# 51_STC89C52RC.net
KiCad netlist of a schematic drawn in EasyEDA Pro
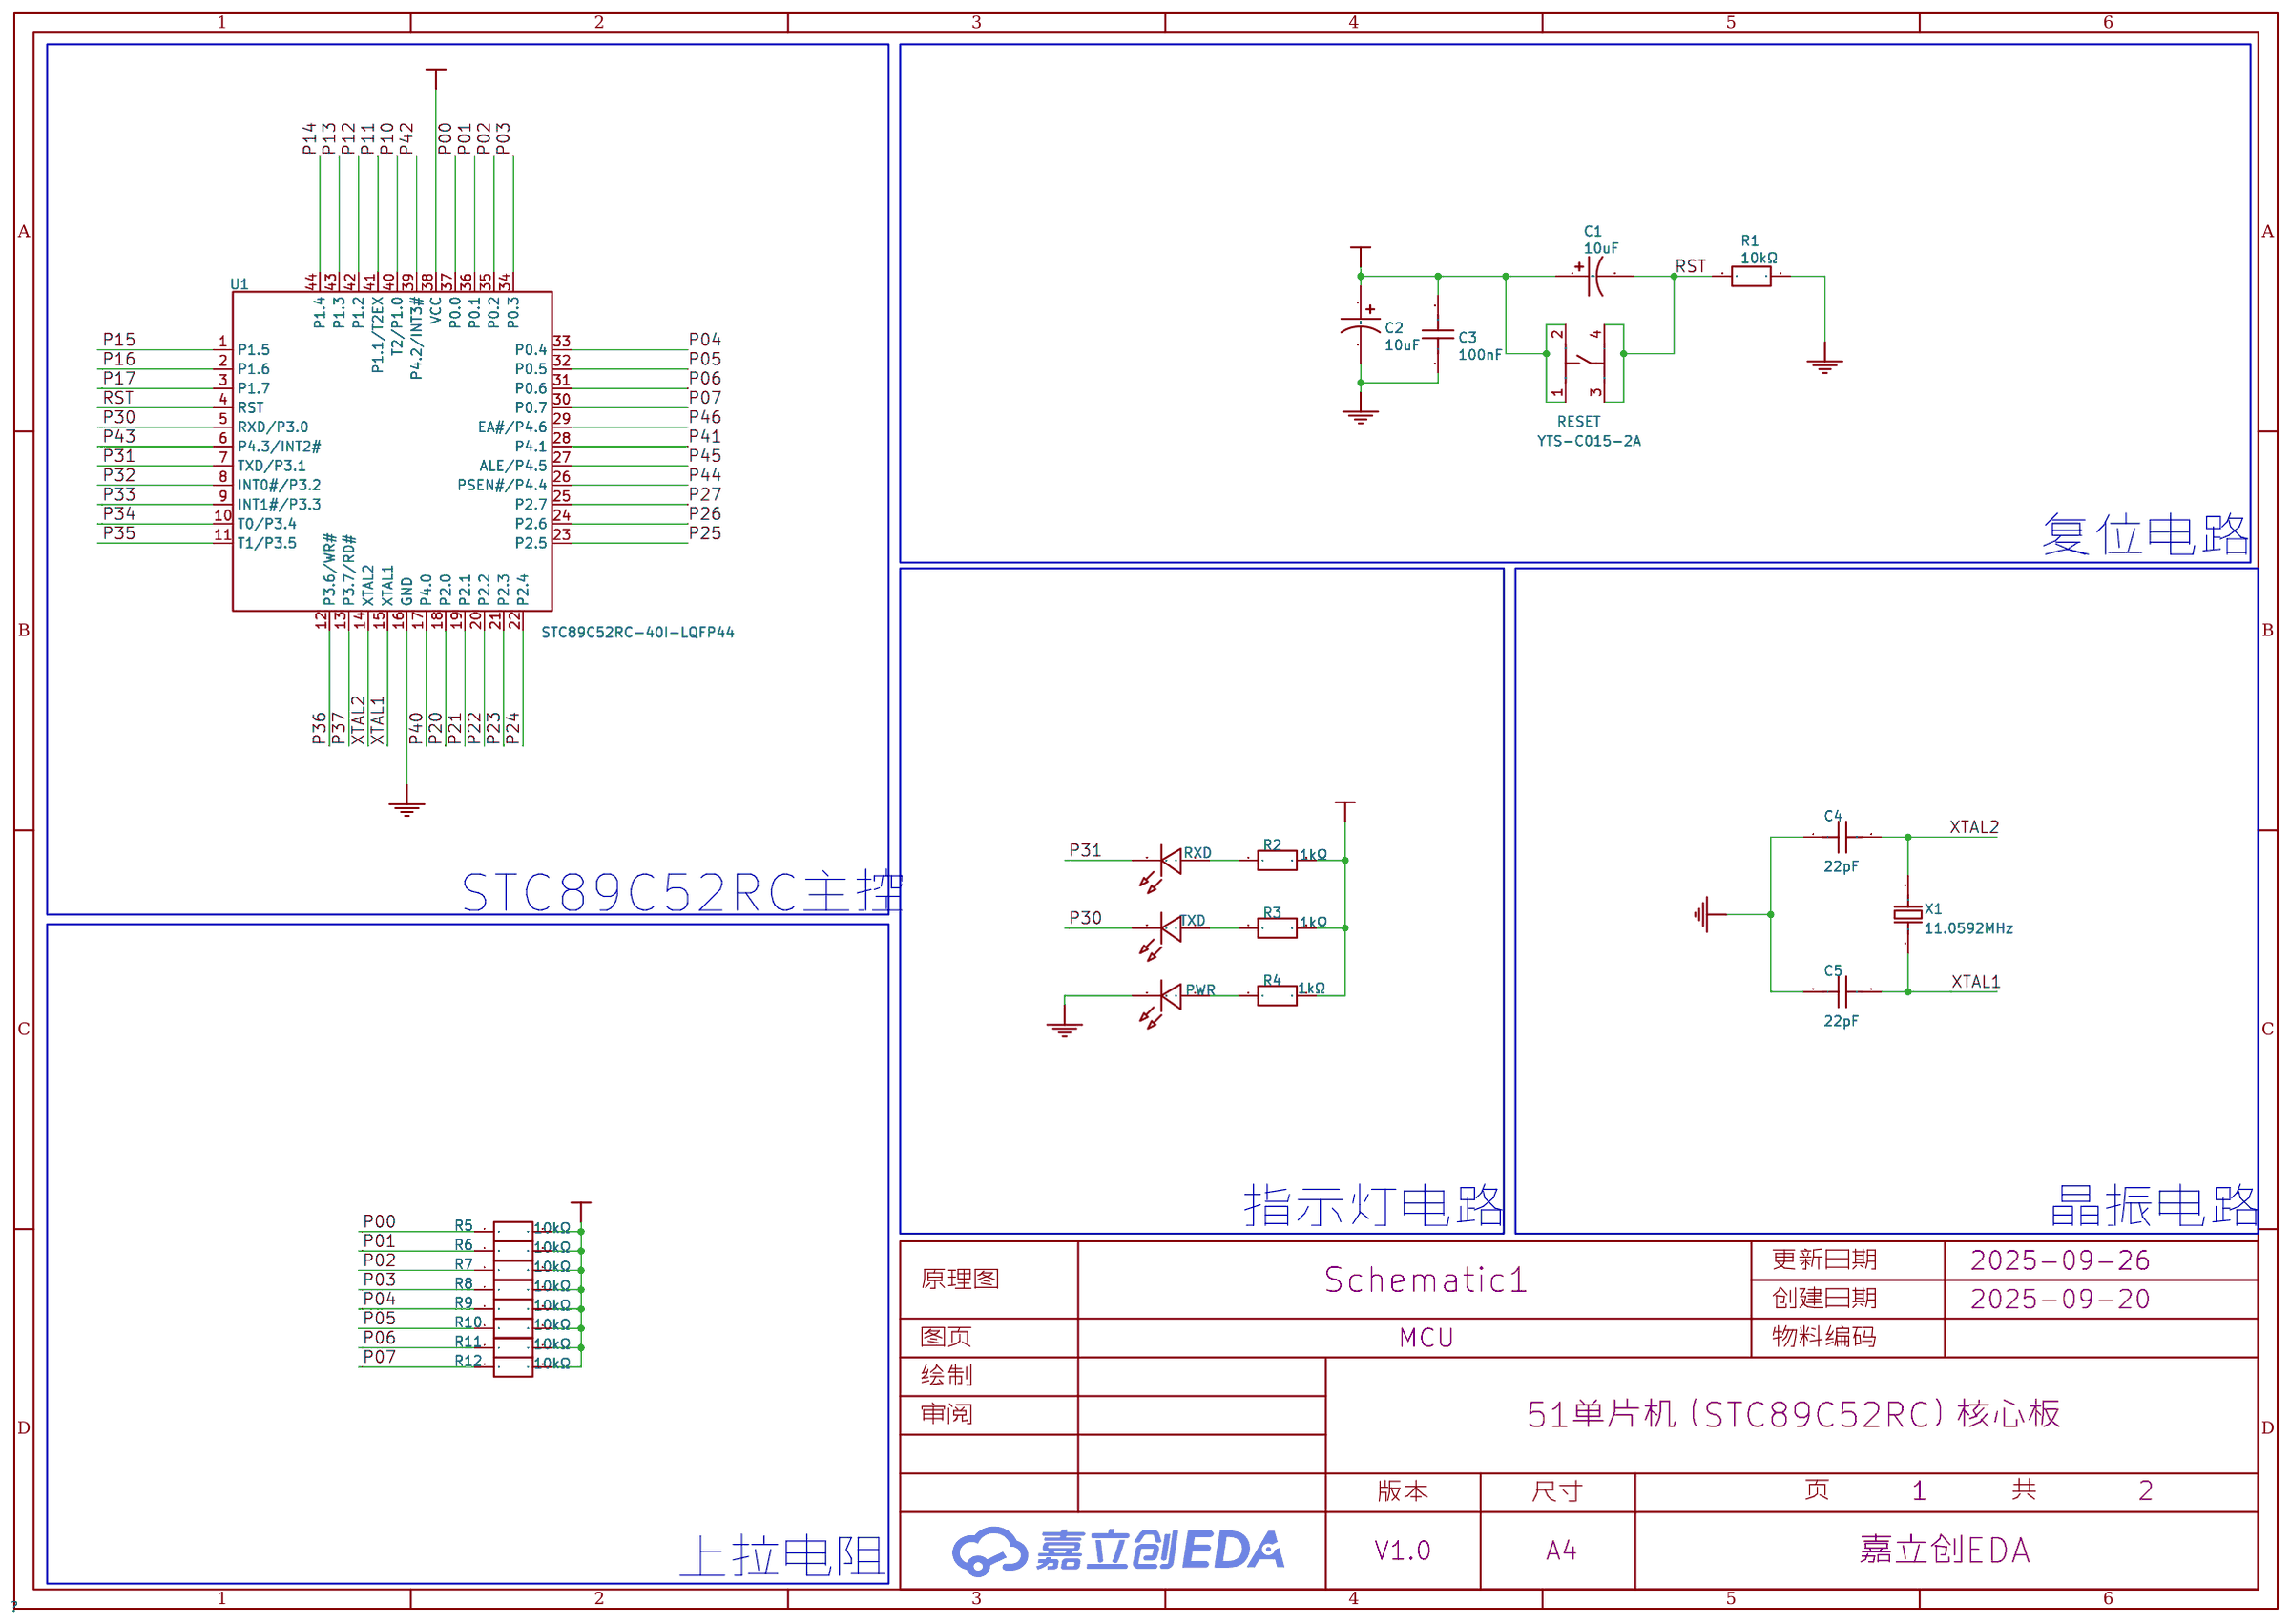
[diagram p0: MCU]
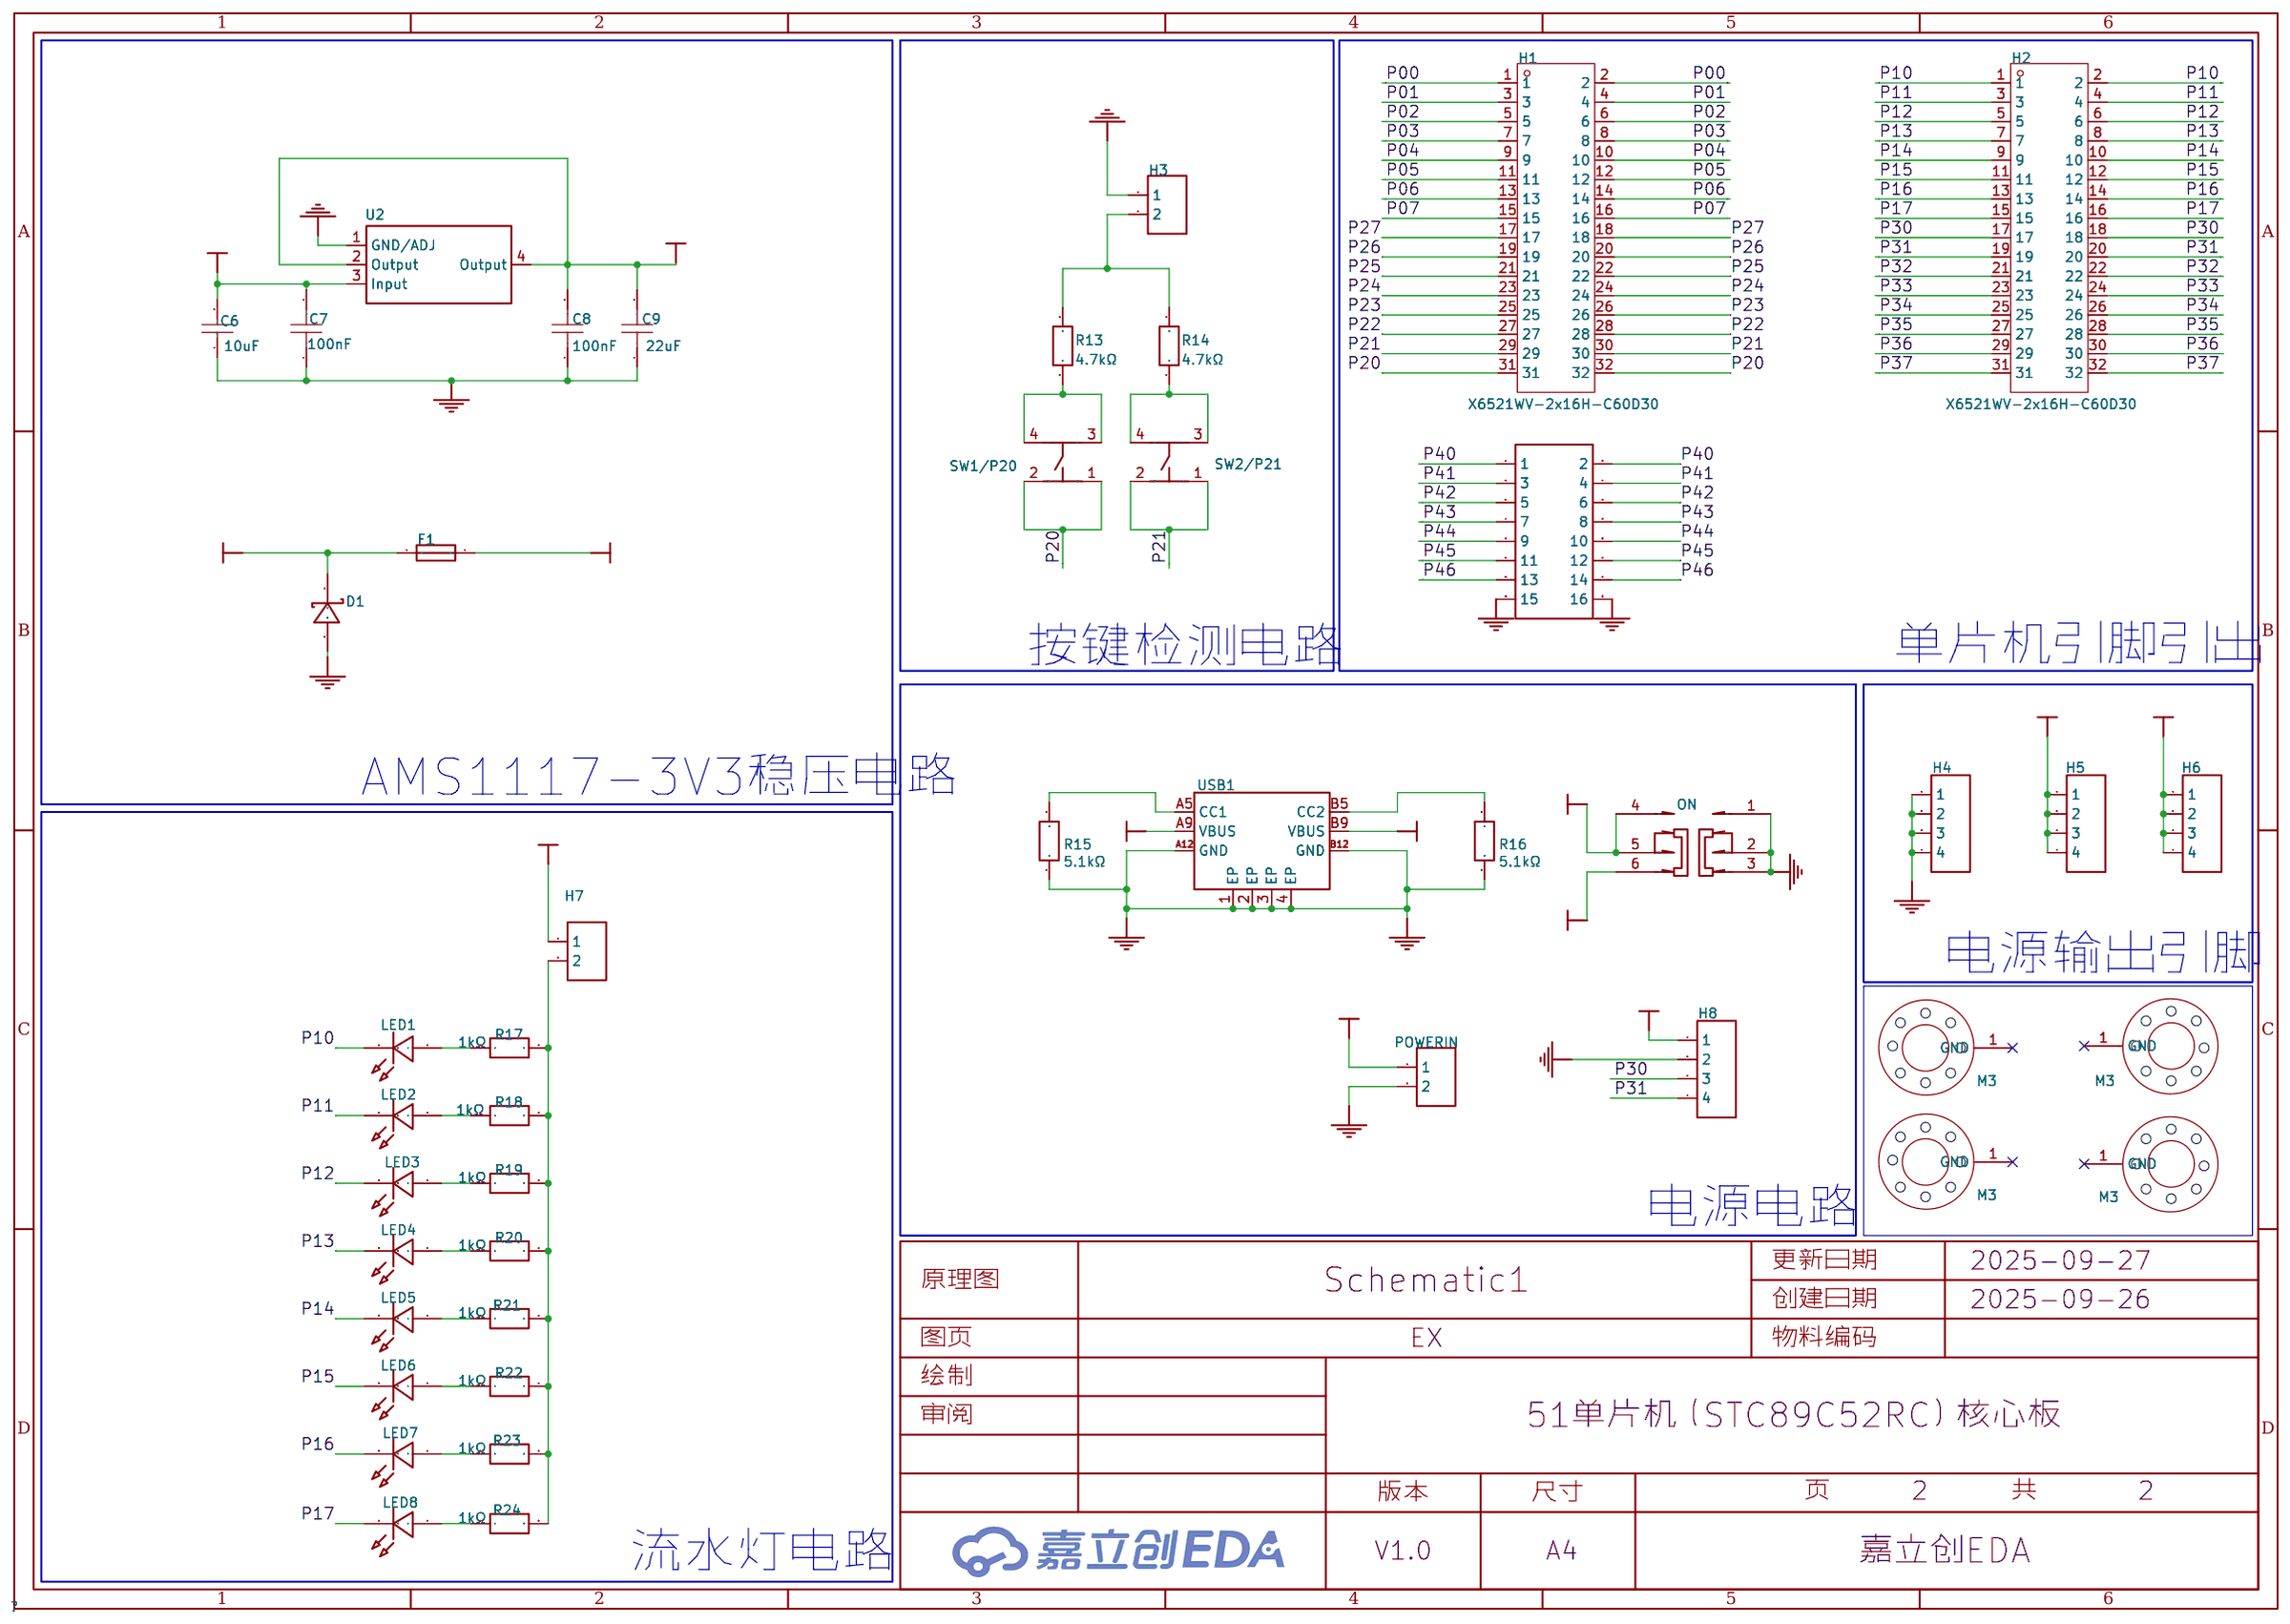
[diagram p1: EX]

(export (version "E")
  (design (tool "Eeschema 10.0.6"))
  (components
    (comp (ref "C1")
      (value "10uF")
      (footprint "easyedapro:CASE-A_3216")
      (fields (field (name "Manufacturer Part") "TAJA106K010RNJ") (field (name "Manufacturer") "Kyocera AVX"))
      (libsource (lib "easyedapro") (part "10u"))
    )
    (comp (ref "C2")
      (value "10uF")
      (footprint "easyedapro:CASE-A_3216")
      (fields (field (name "Manufacturer Part") "TAJA106K010RNJ") (field (name "Manufacturer") "Kyocera AVX"))
      (libsource (lib "") (part "10u_1"))
    )
    (comp (ref "C3")
      (value "100nF")
      (footprint "easyedapro:C0805")
      (fields
        (field (name "Manufacturer Part") "CC0805KRX7R9BB104")
        (field (name "Manufacturer") "YAGEO(国巨)")
      )
      (libsource (lib "easyedapro") (part "0.1u"))
    )
    (comp (ref "C4")
      (value "22pF")
      (footprint "easyedapro:C0805")
      (fields
        (field (name "Manufacturer Part") "CL21C220JBANNNC")
        (field (name "Manufacturer") "SAMSUNG(三星)")
      )
      (libsource (lib "easyedapro") (part "22p"))
    )
    (comp (ref "C5")
      (value "22pF")
      (footprint "easyedapro:C0805")
      (fields
        (field (name "Manufacturer Part") "CL21C220JBANNNC")
        (field (name "Manufacturer") "SAMSUNG(三星)")
      )
      (libsource (lib "easyedapro") (part "22p"))
    )
    (comp (ref "PWR")
      (value "D-B080508B1-KS2")
      (footprint "easyedapro:LED0805_BLUE")
      (fields (field (name "Manufacturer") "ARKLED(方舟)"))
      (libsource (lib "easyedapro") (part "LED-0805_B"))
    )
    (comp (ref "R1")
      (value "10kΩ")
      (footprint "easyedapro:R0805")
      (fields
        (field (name "Manufacturer Part") "0805W8F1002T5E")
        (field (name "Manufacturer") "UNI-ROYAL(厚声)")
      )
      (libsource (lib "easyedapro") (part "10k"))
    )
    (comp (ref "R2")
      (value "1kΩ")
      (footprint "easyedapro:R0805")
      (fields
        (field (name "Manufacturer Part") "0805W8F1001T5E")
        (field (name "Manufacturer") "UNI-ROYAL(厚声)")
      )
      (libsource (lib "easyedapro") (part "1k"))
    )
    (comp (ref "R3")
      (value "1kΩ")
      (footprint "easyedapro:R0805")
      (fields
        (field (name "Manufacturer Part") "0805W8F1001T5E")
        (field (name "Manufacturer") "UNI-ROYAL(厚声)")
      )
      (libsource (lib "easyedapro") (part "1k"))
    )
    (comp (ref "R4")
      (value "1kΩ")
      (footprint "easyedapro:R0805")
      (fields
        (field (name "Manufacturer Part") "0805W8F1001T5E")
        (field (name "Manufacturer") "UNI-ROYAL(厚声)")
      )
      (libsource (lib "easyedapro") (part "1k"))
    )
    (comp (ref "R5")
      (value "10kΩ")
      (footprint "easyedapro:R0805")
      (fields
        (field (name "Manufacturer Part") "0805W8F1002T5E")
        (field (name "Manufacturer") "UNI-ROYAL(厚声)")
      )
      (libsource (lib "easyedapro") (part "10k"))
    )
    (comp (ref "R6")
      (value "10kΩ")
      (footprint "easyedapro:R0805")
      (fields
        (field (name "Manufacturer Part") "0805W8F1002T5E")
        (field (name "Manufacturer") "UNI-ROYAL(厚声)")
      )
      (libsource (lib "easyedapro") (part "10k"))
    )
    (comp (ref "R7")
      (value "10kΩ")
      (footprint "easyedapro:R0805")
      (fields
        (field (name "Manufacturer Part") "0805W8F1002T5E")
        (field (name "Manufacturer") "UNI-ROYAL(厚声)")
      )
      (libsource (lib "easyedapro") (part "10k"))
    )
    (comp (ref "R8")
      (value "10kΩ")
      (footprint "easyedapro:R0805")
      (fields
        (field (name "Manufacturer Part") "0805W8F1002T5E")
        (field (name "Manufacturer") "UNI-ROYAL(厚声)")
      )
      (libsource (lib "easyedapro") (part "10k"))
    )
    (comp (ref "R9")
      (value "10kΩ")
      (footprint "easyedapro:R0805")
      (fields
        (field (name "Manufacturer Part") "0805W8F1002T5E")
        (field (name "Manufacturer") "UNI-ROYAL(厚声)")
      )
      (libsource (lib "easyedapro") (part "10k"))
    )
    (comp (ref "R10")
      (value "10kΩ")
      (footprint "easyedapro:R0805")
      (fields
        (field (name "Manufacturer Part") "0805W8F1002T5E")
        (field (name "Manufacturer") "UNI-ROYAL(厚声)")
      )
      (libsource (lib "easyedapro") (part "10k"))
    )
    (comp (ref "R11")
      (value "10kΩ")
      (footprint "easyedapro:R0805")
      (fields
        (field (name "Manufacturer Part") "0805W8F1002T5E")
        (field (name "Manufacturer") "UNI-ROYAL(厚声)")
      )
      (libsource (lib "easyedapro") (part "10k"))
    )
    (comp (ref "R12")
      (value "10kΩ")
      (footprint "easyedapro:R0805")
      (fields
        (field (name "Manufacturer Part") "0805W8F1002T5E")
        (field (name "Manufacturer") "UNI-ROYAL(厚声)")
      )
      (libsource (lib "easyedapro") (part "10k"))
    )
    (comp (ref "RESET")
      (value "YTS-C015-2A")
      (footprint "easyedapro:SW-SMD_4P-L4.5-W4.5-P3.00-LS6.8")
      (fields (field (name "Manufacturer") "YIYUAN(怡远)"))
      (libsource (lib "easyedapro") (part "YTS-C015-2A COPY"))
    )
    (comp (ref "RXD")
      (value "D-B080508B1-KS2")
      (footprint "easyedapro:LED0805_BLUE")
      (fields (field (name "Manufacturer") "ARKLED(方舟)"))
      (libsource (lib "easyedapro") (part "LED-0805_B"))
    )
    (comp (ref "TXD")
      (value "D-B080508B1-KS2")
      (footprint "easyedapro:LED0805_BLUE")
      (fields (field (name "Manufacturer") "ARKLED(方舟)"))
      (libsource (lib "easyedapro") (part "LED-0805_B"))
    )
    (comp (ref "U1")
      (value "STC89C52RC-40I-LQFP44")
      (footprint "easyedapro:LQFP-44_L10.0-W10.0-P0.80-LS12.0-BL")
      (fields (field (name "Manufacturer") "STC"))
      (libsource (lib "easyedapro") (part "STC89C52RC-40I_C8707"))
    )
    (comp (ref "X1")
      (value "11.0592MHz")
      (footprint "easyedapro:HC-49US_L11.5-W4.5-P4.88")
      (fields
        (field (name "Manufacturer Part") "TAXD11.0592M2GLFBET2T")
        (field (name "Manufacturer") "YJX(雅晶鑫)")
      )
      (libsource (lib "easyedapro") (part "11.0592MHz"))
    )
    (comp (ref "C6")
      (value "10uF")
      (footprint "easyedapro:C0805")
      (description "容值:10uF;精度:±10%;额定电压:16V;温度系数:X5R;")
      (fields
        (field (name "Manufacturer Part") "CL21A106KOQNNNE")
        (field (name "Manufacturer") "SAMSUNG(三星)")
      )
      (libsource (lib "easyedapro") (part "CL21A106KOQNNNE"))
    )
    (comp (ref "C7")
      (value "100nF")
      (footprint "easyedapro:C0805")
      (description "容值:100nF;精度:±10%;额定电压:50V;温度系数:X7R;")
      (fields
        (field (name "Manufacturer Part") "FCC0805B104K500DT")
        (field (name "Manufacturer") "FOJAN(富捷)")
      )
      (libsource (lib "easyedapro") (part "FCC0805B104K500DT"))
    )
    (comp (ref "C8")
      (value "100nF")
      (footprint "easyedapro:C0805")
      (description "容值:100nF;精度:±10%;额定电压:50V;温度系数:X7R;")
      (fields
        (field (name "Manufacturer Part") "FCC0805B104K500DT")
        (field (name "Manufacturer") "FOJAN(富捷)")
      )
      (libsource (lib "easyedapro") (part "FCC0805B104K500DT"))
    )
    (comp (ref "C9")
      (value "22uF")
      (footprint "easyedapro:C0805")
      (description "容值:22uF;精度:±20%;额定电压:25V;温度系数:X5R;")
      (fields
        (field (name "Manufacturer Part") "FCC0805X226M250FT")
        (field (name "Manufacturer") "FOJAN(富捷)")
      )
      (libsource (lib "easyedapro") (part "FCC0805X226M250FT"))
    )
    (comp (ref "D1")
      (value "1N5819W")
      (footprint "easyedapro:SOD-123F_L2.8-W1.8-LS3.7-RD")
      (fields (field (name "Manufacturer") "Shandong Jingdao Microelectronics"))
      (libsource (lib "easyedapro") (part "1N5819W"))
    )
    (comp (ref "F1")
      (value "FSMD050-1206-R")
      (footprint "easyedapro:F1206")
      (fields (field (name "Manufacturer") "Fuzetec Tech"))
      (libsource (lib "easyedapro") (part "FSMD050-1206-R"))
    )
    (comp (ref "H1")
      (value "X6521WV-2x16H-C60D30")
      (footprint "easyedapro:HDR-TH_32P-2.54-V-M-R2-C16-S2.54")
      (fields (field (name "Manufacturer") "XKB Connection(中国星坤)"))
      (libsource (lib "easyedapro") (part "X6521WV-2×16H-C30D60"))
    )
    (comp (ref "H2")
      (value "X6521WV-2x16H-C60D30")
      (footprint "easyedapro:HDR-TH_32P-2.54-V-M-R2-C16-S2.54")
      (fields (field (name "Manufacturer") "XKB Connection(中国星坤)"))
      (libsource (lib "easyedapro") (part "X6521WV-2×16H-C30D60"))
    )
    (comp (ref "H3")
      (value "2.54-1*2P母")
      (footprint "easyedapro:HDR-M-2.54_1X2")
      (libsource (lib "") (part "HDR-F-2.54_1x2_1"))
    )
    (comp (ref "H4")
      (value "A2541HWV-4P")
      (footprint "easyedapro:HDR-F-2.54_1X4")
      (libsource (lib "easyedapro") (part "HDR-F-2.54_1x4"))
    )
    (comp (ref "H5")
      (value "A2541HWV-4P")
      (footprint "easyedapro:HDR-F-2.54_1X4")
      (libsource (lib "easyedapro") (part "HDR-F-2.54_1x4"))
    )
    (comp (ref "H6")
      (value "A2541HWV-4P")
      (footprint "easyedapro:HDR-F-2.54_1X4")
      (libsource (lib "easyedapro") (part "HDR-F-2.54_1x4"))
    )
    (comp (ref "H7")
      (value "2.54-1*2P母")
      (footprint "easyedapro:HDR-M-2.54_1X2")
      (libsource (lib "easyedapro") (part "HDR-F-2.54_1x2"))
    )
    (comp (ref "H8")
      (value "A2541HWV-4P")
      (footprint "easyedapro:HDR-F-2.54_1X4")
      (libsource (lib "easyedapro") (part "HDR-F-2.54_1x4"))
    )
    (comp (ref "hole1")
      (value "M3")
      (footprint "easyedapro:m3梅花孔")
      (description "梅花螺丝孔")
      (libsource (lib "easyedapro") (part "m3_梅花螺丝孔"))
    )
    (comp (ref "hole2")
      (value "M3")
      (footprint "easyedapro:m3梅花孔")
      (description "梅花螺丝孔")
      (libsource (lib "easyedapro") (part "m3_梅花螺丝孔"))
    )
    (comp (ref "hole3")
      (value "M3")
      (footprint "easyedapro:m3梅花孔")
      (description "梅花螺丝孔")
      (libsource (lib "easyedapro") (part "m3_梅花螺丝孔"))
    )
    (comp (ref "hole4")
      (value "M3")
      (footprint "easyedapro:m3梅花孔")
      (description "梅花螺丝孔")
      (libsource (lib "easyedapro") (part "m3_梅花螺丝孔"))
    )
    (comp (ref "J1")
      (value "2.54-2*8P针")
      (footprint "easyedapro:HDR-M-2.54_2X8")
      (fields (field (name "Manufacturer") "BOOMELE(博穆精密)"))
      (libsource (lib "easyedapro") (part "HDR-M-2.54_2x8"))
    )
    (comp (ref "LED1")
      (value "D-B080508B1-KS2")
      (footprint "easyedapro:LED0805_BLUE")
      (fields (field (name "Manufacturer") "方舟 ARKLED"))
      (libsource (lib "easyedapro") (part "LED-0805_B"))
    )
    (comp (ref "LED2")
      (value "D-B080508B1-KS2")
      (footprint "easyedapro:LED0805_BLUE")
      (fields (field (name "Manufacturer") "方舟 ARKLED"))
      (libsource (lib "easyedapro") (part "LED-0805_B"))
    )
    (comp (ref "LED3")
      (value "D-B080508B1-KS2")
      (footprint "easyedapro:LED0805_BLUE")
      (fields (field (name "Manufacturer") "方舟 ARKLED"))
      (libsource (lib "easyedapro") (part "LED-0805_B"))
    )
    (comp (ref "LED4")
      (value "D-B080508B1-KS2")
      (footprint "easyedapro:LED0805_BLUE")
      (fields (field (name "Manufacturer") "方舟 ARKLED"))
      (libsource (lib "easyedapro") (part "LED-0805_B"))
    )
    (comp (ref "LED5")
      (value "D-B080508B1-KS2")
      (footprint "easyedapro:LED0805_BLUE")
      (fields (field (name "Manufacturer") "方舟 ARKLED"))
      (libsource (lib "easyedapro") (part "LED-0805_B"))
    )
    (comp (ref "LED6")
      (value "D-B080508B1-KS2")
      (footprint "easyedapro:LED0805_BLUE")
      (fields (field (name "Manufacturer") "方舟 ARKLED"))
      (libsource (lib "easyedapro") (part "LED-0805_B"))
    )
    (comp (ref "LED7")
      (value "D-B080508B1-KS2")
      (footprint "easyedapro:LED0805_BLUE")
      (fields (field (name "Manufacturer") "方舟 ARKLED"))
      (libsource (lib "easyedapro") (part "LED-0805_B"))
    )
    (comp (ref "LED8")
      (value "D-B080508B1-KS2")
      (footprint "easyedapro:LED0805_BLUE")
      (fields (field (name "Manufacturer") "方舟 ARKLED"))
      (libsource (lib "easyedapro") (part "LED-0805_B"))
    )
    (comp (ref "ON")
      (value "SS-3235S-L1")
      (footprint "easyedapro:SW-SMD_SS-3235S-LX")
      (description "电路结构:双刀双掷;安装方式:卧贴;开关颜色:黑色;额定电流:50mA;额定电压:12V;工作寿命:1万次;")
      (fields (field (name "Manufacturer") "XKB Connection(中国星坤)"))
      (libsource (lib "easyedapro") (part "SS-3235S-L1"))
    )
    (comp (ref "POWERIN")
      (value "2.54-1*2P母")
      (footprint "easyedapro:HDR-M-2.54_1X2")
      (libsource (lib "easyedapro") (part "HDR-F-2.54_1x2"))
    )
    (comp (ref "R13")
      (value "4.7kΩ")
      (footprint "easyedapro:R0805")
      (fields (field (name "Manufacturer") "UNI-ROYAL(厚声)"))
      (libsource (lib "easyedapro") (part "4.7K"))
    )
    (comp (ref "R14")
      (value "4.7kΩ")
      (footprint "easyedapro:R0805")
      (fields (field (name "Manufacturer") "UNI-ROYAL(厚声)"))
      (libsource (lib "easyedapro") (part "4.7K"))
    )
    (comp (ref "R15")
      (value "5.1kΩ")
      (footprint "easyedapro:R0805")
      (fields (field (name "Manufacturer") "UNI-ROYAL(厚声)"))
      (libsource (lib "easyedapro") (part "5.1k"))
    )
    (comp (ref "R16")
      (value "5.1kΩ")
      (footprint "easyedapro:R0805")
      (fields (field (name "Manufacturer") "UNI-ROYAL(厚声)"))
      (libsource (lib "easyedapro") (part "5.1k"))
    )
    (comp (ref "R17")
      (value "1kΩ")
      (footprint "easyedapro:R0805")
      (fields (field (name "Manufacturer") "UNI-ROYAL(厚声)"))
      (libsource (lib "easyedapro") (part "1k"))
    )
    (comp (ref "R18")
      (value "1kΩ")
      (footprint "easyedapro:R0805")
      (fields (field (name "Manufacturer") "UNI-ROYAL(厚声)"))
      (libsource (lib "easyedapro") (part "1k"))
    )
    (comp (ref "R19")
      (value "1kΩ")
      (footprint "easyedapro:R0805")
      (fields (field (name "Manufacturer") "UNI-ROYAL(厚声)"))
      (libsource (lib "easyedapro") (part "1k"))
    )
    (comp (ref "R20")
      (value "1kΩ")
      (footprint "easyedapro:R0805")
      (fields (field (name "Manufacturer") "UNI-ROYAL(厚声)"))
      (libsource (lib "easyedapro") (part "1k"))
    )
    (comp (ref "R21")
      (value "1kΩ")
      (footprint "easyedapro:R0805")
      (fields (field (name "Manufacturer") "UNI-ROYAL(厚声)"))
      (libsource (lib "easyedapro") (part "1k"))
    )
    (comp (ref "R22")
      (value "1kΩ")
      (footprint "easyedapro:R0805")
      (fields (field (name "Manufacturer") "UNI-ROYAL(厚声)"))
      (libsource (lib "easyedapro") (part "1k"))
    )
    (comp (ref "R23")
      (value "1kΩ")
      (footprint "easyedapro:R0805")
      (fields (field (name "Manufacturer") "UNI-ROYAL(厚声)"))
      (libsource (lib "easyedapro") (part "1k"))
    )
    (comp (ref "R24")
      (value "1kΩ")
      (footprint "easyedapro:R0805")
      (fields (field (name "Manufacturer") "UNI-ROYAL(厚声)"))
      (libsource (lib "easyedapro") (part "1k"))
    )
    (comp (ref "SW1/P20")
      (value "YTS-C015-2A")
      (footprint "easyedapro:SW-SMD_4P-L4.5-W4.5-P3.00-LS6.8")
      (fields (field (name "Manufacturer") "YIYUAN(怡远)"))
      (libsource (lib "easyedapro") (part "YTS-C015-2A COPY"))
    )
    (comp (ref "SW2/P21")
      (value "YTS-C015-2A")
      (footprint "easyedapro:SW-SMD_4P-L4.5-W4.5-P3.00-LS6.8")
      (fields (field (name "Manufacturer") "YIYUAN(怡远)"))
      (libsource (lib "easyedapro") (part "YTS-C015-2A COPY"))
    )
    (comp (ref "U2")
      (value "AMS1117-3.3")
      (footprint "easyedapro:SOT-223-4_L6.5-W3.5-P2.30-LS7.0-BR")
      (fields (field (name "Manufacturer") "KEXIN"))
      (libsource (lib "easyedapro") (part "AMS1117"))
    )
    (comp (ref "USB1")
      (value "KH-TYPE-C-6P")
      (footprint "easyedapro:TYPE-C-SMD_TYPE-C-31-M-16")
      (fields (field (name "Manufacturer") "Shenzhen Kinghelm Elec"))
      (libsource (lib "easyedapro") (part "KH-TYPE-C-6P"))
    )
  )
  (nets
    (net (code "1") (name "+5V") (class "Default")
      (node (ref "C1") (pin "1") (pinfunction "1_1") (pintype "unspecified"))
      (node (ref "C2") (pin "1") (pinfunction "1_1") (pintype "unspecified"))
      (node (ref "C3") (pin "2") (pinfunction "2_2") (pintype "unspecified"))
      (node (ref "C6") (pin "2") (pinfunction "2_2") (pintype "input"))
      (node (ref "C7") (pin "2") (pinfunction "2_2") (pintype "unspecified"))
      (node (ref "D1") (pin "1") (pinfunction "1_1") (pintype "unspecified"))
      (node (ref "F1") (pin "2") (pinfunction "2_2") (pintype "unspecified"))
      (node (ref "H5") (pin "1") (pinfunction "1_1") (pintype "unspecified"))
      (node (ref "H5") (pin "2") (pinfunction "2_2") (pintype "unspecified"))
      (node (ref "H5") (pin "3") (pinfunction "3_3") (pintype "unspecified"))
      (node (ref "H5") (pin "4") (pinfunction "4_4") (pintype "unspecified"))
      (node (ref "H7") (pin "1") (pinfunction "1_1") (pintype "input"))
      (node (ref "H8") (pin "1") (pinfunction "1_1") (pintype "unspecified"))
      (node (ref "R10") (pin "2") (pinfunction "2_2") (pintype "unspecified"))
      (node (ref "R11") (pin "2") (pinfunction "2_2") (pintype "unspecified"))
      (node (ref "R12") (pin "2") (pinfunction "2_2") (pintype "unspecified"))
      (node (ref "R2") (pin "2") (pinfunction "2_2") (pintype "unspecified"))
      (node (ref "R3") (pin "2") (pinfunction "2_2") (pintype "unspecified"))
      (node (ref "R4") (pin "2") (pinfunction "2_2") (pintype "unspecified"))
      (node (ref "R5") (pin "2") (pinfunction "2_2") (pintype "unspecified"))
      (node (ref "R6") (pin "2") (pinfunction "2_2") (pintype "unspecified"))
      (node (ref "R7") (pin "2") (pinfunction "2_2") (pintype "unspecified"))
      (node (ref "R8") (pin "2") (pinfunction "2_2") (pintype "unspecified"))
      (node (ref "R9") (pin "2") (pinfunction "2_2") (pintype "unspecified"))
      (node (ref "RESET") (pin "1") (pinfunction "1_1") (pintype "unspecified"))
      (node (ref "RESET") (pin "2") (pinfunction "2_2") (pintype "unspecified"))
      (node (ref "U1") (pin "38") (pinfunction "VCC_38") (pintype "unspecified"))
      (node (ref "U2") (pin "3") (pinfunction "Input_3") (pintype "unspecified"))
    )
    (net (code "2") (name "3V3") (class "Default")
      (node (ref "C8") (pin "2") (pinfunction "2_2") (pintype "unspecified"))
      (node (ref "C9") (pin "2") (pinfunction "2_2") (pintype "unspecified"))
      (node (ref "H6") (pin "1") (pinfunction "1_1") (pintype "unspecified"))
      (node (ref "H6") (pin "2") (pinfunction "2_2") (pintype "unspecified"))
      (node (ref "H6") (pin "3") (pinfunction "3_3") (pintype "unspecified"))
      (node (ref "H6") (pin "4") (pinfunction "4_4") (pintype "unspecified"))
      (node (ref "U2") (pin "2") (pinfunction "Output_2") (pintype "unspecified"))
      (node (ref "U2") (pin "4") (pinfunction "Output_4") (pintype "unspecified"))
    )
    (net (code "3") (name "GND") (class "Default")
      (node (ref "C2") (pin "2") (pinfunction "2_2") (pintype "unspecified"))
      (node (ref "C3") (pin "1") (pinfunction "1_1") (pintype "unspecified"))
      (node (ref "C4") (pin "1") (pinfunction "1_1") (pintype "unspecified"))
      (node (ref "C5") (pin "2") (pinfunction "2_2") (pintype "unspecified"))
      (node (ref "C6") (pin "1") (pinfunction "1_1") (pintype "input"))
      (node (ref "C7") (pin "1") (pinfunction "1_1") (pintype "unspecified"))
      (node (ref "C8") (pin "1") (pinfunction "1_1") (pintype "unspecified"))
      (node (ref "C9") (pin "1") (pinfunction "1_1") (pintype "unspecified"))
      (node (ref "D1") (pin "2") (pinfunction "2_2") (pintype "unspecified"))
      (node (ref "H3") (pin "1") (pinfunction "1_1") (pintype "input"))
      (node (ref "H4") (pin "1") (pinfunction "1_1") (pintype "unspecified"))
      (node (ref "H4") (pin "2") (pinfunction "2_2") (pintype "unspecified"))
      (node (ref "H4") (pin "3") (pinfunction "3_3") (pintype "unspecified"))
      (node (ref "H4") (pin "4") (pinfunction "4_4") (pintype "unspecified"))
      (node (ref "H8") (pin "2") (pinfunction "2_2") (pintype "unspecified"))
      (node (ref "J1") (pin "15") (pinfunction "15_15") (pintype "input"))
      (node (ref "J1") (pin "16") (pinfunction "16_16") (pintype "input"))
      (node (ref "ON") (pin "1") (pinfunction "1_1") (pintype "unspecified"))
      (node (ref "ON") (pin "2") (pinfunction "2_2") (pintype "unspecified"))
      (node (ref "ON") (pin "3") (pinfunction "3_3") (pintype "unspecified"))
      (node (ref "POWERIN") (pin "2") (pinfunction "2_2") (pintype "input"))
      (node (ref "PWR") (pin "2") (pinfunction "2_2") (pintype "unspecified"))
      (node (ref "R1") (pin "2") (pinfunction "2_2") (pintype "unspecified"))
      (node (ref "R15") (pin "1") (pinfunction "1_1") (pintype "unspecified"))
      (node (ref "R16") (pin "1") (pinfunction "1_1") (pintype "unspecified"))
      (node (ref "U1") (pin "16") (pinfunction "GND_16") (pintype "unspecified"))
      (node (ref "U2") (pin "1") (pinfunction "GND/ADJ_1") (pintype "unspecified"))
      (node (ref "USB1") (pin "1") (pinfunction "EP_1") (pintype "unspecified"))
      (node (ref "USB1") (pin "2") (pinfunction "EP_2") (pintype "unspecified"))
      (node (ref "USB1") (pin "3") (pinfunction "EP_3") (pintype "unspecified"))
      (node (ref "USB1") (pin "4") (pinfunction "EP_4") (pintype "unspecified"))
      (node (ref "USB1") (pin "A12") (pinfunction "GND_A12") (pintype "unspecified"))
      (node (ref "USB1") (pin "B12") (pinfunction "GND_B12") (pintype "unspecified"))
    )
    (net (code "4") (name "Net-(H3-Pad2)") (class "Default")
      (node (ref "H3") (pin "2") (pinfunction "2_2") (pintype "input"))
      (node (ref "R13") (pin "2") (pinfunction "2_2") (pintype "unspecified"))
      (node (ref "R14") (pin "2") (pinfunction "2_2") (pintype "unspecified"))
    )
    (net (code "5") (name "Net-(H7-Pad2)") (class "Default")
      (node (ref "H7") (pin "2") (pinfunction "2_2") (pintype "input"))
      (node (ref "R17") (pin "2") (pinfunction "2_2") (pintype "unspecified"))
      (node (ref "R18") (pin "2") (pinfunction "2_2") (pintype "unspecified"))
      (node (ref "R19") (pin "2") (pinfunction "2_2") (pintype "unspecified"))
      (node (ref "R20") (pin "2") (pinfunction "2_2") (pintype "unspecified"))
      (node (ref "R21") (pin "2") (pinfunction "2_2") (pintype "unspecified"))
      (node (ref "R22") (pin "2") (pinfunction "2_2") (pintype "unspecified"))
      (node (ref "R23") (pin "2") (pinfunction "2_2") (pintype "unspecified"))
      (node (ref "R24") (pin "2") (pinfunction "2_2") (pintype "unspecified"))
    )
    (net (code "6") (name "Net-(LED1-Pad1)") (class "Default")
      (node (ref "LED1") (pin "1") (pinfunction "1_1") (pintype "unspecified"))
      (node (ref "R17") (pin "1") (pinfunction "1_1") (pintype "unspecified"))
    )
    (net (code "7") (name "Net-(LED2-Pad1)") (class "Default")
      (node (ref "LED2") (pin "1") (pinfunction "1_1") (pintype "unspecified"))
      (node (ref "R18") (pin "1") (pinfunction "1_1") (pintype "unspecified"))
    )
    (net (code "8") (name "Net-(LED3-Pad1)") (class "Default")
      (node (ref "LED3") (pin "1") (pinfunction "1_1") (pintype "unspecified"))
      (node (ref "R19") (pin "1") (pinfunction "1_1") (pintype "unspecified"))
    )
    (net (code "9") (name "Net-(LED4-Pad1)") (class "Default")
      (node (ref "LED4") (pin "1") (pinfunction "1_1") (pintype "unspecified"))
      (node (ref "R20") (pin "1") (pinfunction "1_1") (pintype "unspecified"))
    )
    (net (code "10") (name "Net-(LED5-Pad1)") (class "Default")
      (node (ref "LED5") (pin "1") (pinfunction "1_1") (pintype "unspecified"))
      (node (ref "R21") (pin "1") (pinfunction "1_1") (pintype "unspecified"))
    )
    (net (code "11") (name "Net-(LED6-Pad1)") (class "Default")
      (node (ref "LED6") (pin "1") (pinfunction "1_1") (pintype "unspecified"))
      (node (ref "R22") (pin "1") (pinfunction "1_1") (pintype "unspecified"))
    )
    (net (code "12") (name "Net-(LED7-Pad1)") (class "Default")
      (node (ref "LED7") (pin "1") (pinfunction "1_1") (pintype "unspecified"))
      (node (ref "R23") (pin "1") (pinfunction "1_1") (pintype "unspecified"))
    )
    (net (code "13") (name "Net-(LED8-Pad1)") (class "Default")
      (node (ref "LED8") (pin "1") (pinfunction "1_1") (pintype "unspecified"))
      (node (ref "R24") (pin "1") (pinfunction "1_1") (pintype "unspecified"))
    )
    (net (code "14") (name "Net-(PWR-Pad1)") (class "Default")
      (node (ref "PWR") (pin "1") (pinfunction "1_1") (pintype "unspecified"))
      (node (ref "R4") (pin "1") (pinfunction "1_1") (pintype "unspecified"))
    )
    (net (code "15") (name "Net-(R2-Pad1)") (class "Default")
      (node (ref "R2") (pin "1") (pinfunction "1_1") (pintype "unspecified"))
      (node (ref "RXD") (pin "1") (pinfunction "1_1") (pintype "unspecified"))
    )
    (net (code "16") (name "Net-(R3-Pad1)") (class "Default")
      (node (ref "R3") (pin "1") (pinfunction "1_1") (pintype "unspecified"))
      (node (ref "TXD") (pin "1") (pinfunction "1_1") (pintype "unspecified"))
    )
    (net (code "17") (name "Net-(R13-Pad1)") (class "Default")
      (node (ref "R13") (pin "1") (pinfunction "1_1") (pintype "unspecified"))
      (node (ref "SW1/P20") (pin "3") (pinfunction "3_3") (pintype "unspecified"))
      (node (ref "SW1/P20") (pin "4") (pinfunction "4_4") (pintype "unspecified"))
    )
    (net (code "18") (name "Net-(R14-Pad1)") (class "Default")
      (node (ref "R14") (pin "1") (pinfunction "1_1") (pintype "unspecified"))
      (node (ref "SW2/P21") (pin "3") (pinfunction "3_3") (pintype "unspecified"))
      (node (ref "SW2/P21") (pin "4") (pinfunction "4_4") (pintype "unspecified"))
    )
    (net (code "19") (name "Net-(USB1-CC1)") (class "Default")
      (node (ref "R15") (pin "2") (pinfunction "2_2") (pintype "unspecified"))
      (node (ref "USB1") (pin "A5") (pinfunction "CC1_A5") (pintype "unspecified"))
    )
    (net (code "20") (name "Net-(USB1-CC2)") (class "Default")
      (node (ref "R16") (pin "2") (pinfunction "2_2") (pintype "unspecified"))
      (node (ref "USB1") (pin "B5") (pinfunction "CC2_B5") (pintype "unspecified"))
    )
    (net (code "21") (name "P00") (class "Default")
      (node (ref "H1") (pin "1") (pinfunction "1_1") (pintype "unspecified"))
      (node (ref "H1") (pin "2") (pinfunction "2_2") (pintype "unspecified"))
      (node (ref "R5") (pin "1") (pinfunction "1_1") (pintype "unspecified"))
      (node (ref "U1") (pin "37") (pinfunction "P0.0_37") (pintype "unspecified"))
    )
    (net (code "22") (name "P01") (class "Default")
      (node (ref "H1") (pin "3") (pinfunction "3_3") (pintype "unspecified"))
      (node (ref "H1") (pin "4") (pinfunction "4_4") (pintype "unspecified"))
      (node (ref "R6") (pin "1") (pinfunction "1_1") (pintype "unspecified"))
      (node (ref "U1") (pin "36") (pinfunction "P0.1_36") (pintype "unspecified"))
    )
    (net (code "23") (name "P02") (class "Default")
      (node (ref "H1") (pin "5") (pinfunction "5_5") (pintype "unspecified"))
      (node (ref "H1") (pin "6") (pinfunction "6_6") (pintype "unspecified"))
      (node (ref "R7") (pin "1") (pinfunction "1_1") (pintype "unspecified"))
      (node (ref "U1") (pin "35") (pinfunction "P0.2_35") (pintype "unspecified"))
    )
    (net (code "24") (name "P03") (class "Default")
      (node (ref "H1") (pin "7") (pinfunction "7_7") (pintype "unspecified"))
      (node (ref "H1") (pin "8") (pinfunction "8_8") (pintype "unspecified"))
      (node (ref "R8") (pin "1") (pinfunction "1_1") (pintype "unspecified"))
      (node (ref "U1") (pin "34") (pinfunction "P0.3_34") (pintype "unspecified"))
    )
    (net (code "25") (name "P04") (class "Default")
      (node (ref "H1") (pin "10") (pinfunction "10_10") (pintype "unspecified"))
      (node (ref "H1") (pin "9") (pinfunction "9_9") (pintype "unspecified"))
      (node (ref "R9") (pin "1") (pinfunction "1_1") (pintype "unspecified"))
      (node (ref "U1") (pin "33") (pinfunction "P0.4_33") (pintype "unspecified"))
    )
    (net (code "26") (name "P05") (class "Default")
      (node (ref "H1") (pin "11") (pinfunction "11_11") (pintype "unspecified"))
      (node (ref "H1") (pin "12") (pinfunction "12_12") (pintype "unspecified"))
      (node (ref "R10") (pin "1") (pinfunction "1_1") (pintype "unspecified"))
      (node (ref "U1") (pin "32") (pinfunction "P0.5_32") (pintype "unspecified"))
    )
    (net (code "27") (name "P06") (class "Default")
      (node (ref "H1") (pin "13") (pinfunction "13_13") (pintype "unspecified"))
      (node (ref "H1") (pin "14") (pinfunction "14_14") (pintype "unspecified"))
      (node (ref "R11") (pin "1") (pinfunction "1_1") (pintype "unspecified"))
      (node (ref "U1") (pin "31") (pinfunction "P0.6_31") (pintype "unspecified"))
    )
    (net (code "28") (name "P07") (class "Default")
      (node (ref "H1") (pin "15") (pinfunction "15_15") (pintype "unspecified"))
      (node (ref "H1") (pin "16") (pinfunction "16_16") (pintype "unspecified"))
      (node (ref "R12") (pin "1") (pinfunction "1_1") (pintype "unspecified"))
      (node (ref "U1") (pin "30") (pinfunction "P0.7_30") (pintype "unspecified"))
    )
    (net (code "29") (name "P10") (class "Default")
      (node (ref "H2") (pin "1") (pinfunction "1_1") (pintype "unspecified"))
      (node (ref "H2") (pin "2") (pinfunction "2_2") (pintype "unspecified"))
      (node (ref "LED1") (pin "2") (pinfunction "2_2") (pintype "unspecified"))
      (node (ref "U1") (pin "40") (pinfunction "T2/P1.0_40") (pintype "unspecified"))
    )
    (net (code "30") (name "P11") (class "Default")
      (node (ref "H2") (pin "3") (pinfunction "3_3") (pintype "unspecified"))
      (node (ref "H2") (pin "4") (pinfunction "4_4") (pintype "unspecified"))
      (node (ref "LED2") (pin "2") (pinfunction "2_2") (pintype "unspecified"))
      (node (ref "U1") (pin "41") (pinfunction "P1.1/T2EX_41") (pintype "unspecified"))
    )
    (net (code "31") (name "P12") (class "Default")
      (node (ref "H2") (pin "5") (pinfunction "5_5") (pintype "unspecified"))
      (node (ref "H2") (pin "6") (pinfunction "6_6") (pintype "unspecified"))
      (node (ref "LED3") (pin "2") (pinfunction "2_2") (pintype "unspecified"))
      (node (ref "U1") (pin "42") (pinfunction "P1.2_42") (pintype "unspecified"))
    )
    (net (code "32") (name "P13") (class "Default")
      (node (ref "H2") (pin "7") (pinfunction "7_7") (pintype "unspecified"))
      (node (ref "H2") (pin "8") (pinfunction "8_8") (pintype "unspecified"))
      (node (ref "LED4") (pin "2") (pinfunction "2_2") (pintype "unspecified"))
      (node (ref "U1") (pin "43") (pinfunction "P1.3_43") (pintype "unspecified"))
    )
    (net (code "33") (name "P14") (class "Default")
      (node (ref "H2") (pin "10") (pinfunction "10_10") (pintype "unspecified"))
      (node (ref "H2") (pin "9") (pinfunction "9_9") (pintype "unspecified"))
      (node (ref "LED5") (pin "2") (pinfunction "2_2") (pintype "unspecified"))
      (node (ref "U1") (pin "44") (pinfunction "P1.4_44") (pintype "unspecified"))
    )
    (net (code "34") (name "P15") (class "Default")
      (node (ref "H2") (pin "11") (pinfunction "11_11") (pintype "unspecified"))
      (node (ref "H2") (pin "12") (pinfunction "12_12") (pintype "unspecified"))
      (node (ref "LED6") (pin "2") (pinfunction "2_2") (pintype "unspecified"))
      (node (ref "U1") (pin "1") (pinfunction "P1.5_1") (pintype "unspecified"))
    )
    (net (code "35") (name "P16") (class "Default")
      (node (ref "H2") (pin "13") (pinfunction "13_13") (pintype "unspecified"))
      (node (ref "H2") (pin "14") (pinfunction "14_14") (pintype "unspecified"))
      (node (ref "LED7") (pin "2") (pinfunction "2_2") (pintype "unspecified"))
      (node (ref "U1") (pin "2") (pinfunction "P1.6_2") (pintype "unspecified"))
    )
    (net (code "36") (name "P17") (class "Default")
      (node (ref "H2") (pin "15") (pinfunction "15_15") (pintype "unspecified"))
      (node (ref "H2") (pin "16") (pinfunction "16_16") (pintype "unspecified"))
      (node (ref "LED8") (pin "2") (pinfunction "2_2") (pintype "unspecified"))
      (node (ref "U1") (pin "3") (pinfunction "P1.7_3") (pintype "unspecified"))
    )
    (net (code "37") (name "P20") (class "Default")
      (node (ref "H1") (pin "31") (pinfunction "31_31") (pintype "unspecified"))
      (node (ref "H1") (pin "32") (pinfunction "32_32") (pintype "unspecified"))
      (node (ref "SW1/P20") (pin "1") (pinfunction "1_1") (pintype "unspecified"))
      (node (ref "SW1/P20") (pin "2") (pinfunction "2_2") (pintype "unspecified"))
      (node (ref "U1") (pin "18") (pinfunction "P2.0_18") (pintype "unspecified"))
    )
    (net (code "38") (name "P21") (class "Default")
      (node (ref "H1") (pin "29") (pinfunction "29_29") (pintype "unspecified"))
      (node (ref "H1") (pin "30") (pinfunction "30_30") (pintype "unspecified"))
      (node (ref "SW2/P21") (pin "1") (pinfunction "1_1") (pintype "unspecified"))
      (node (ref "SW2/P21") (pin "2") (pinfunction "2_2") (pintype "unspecified"))
      (node (ref "U1") (pin "19") (pinfunction "P2.1_19") (pintype "unspecified"))
    )
    (net (code "39") (name "P22") (class "Default")
      (node (ref "H1") (pin "27") (pinfunction "27_27") (pintype "unspecified"))
      (node (ref "H1") (pin "28") (pinfunction "28_28") (pintype "unspecified"))
      (node (ref "U1") (pin "20") (pinfunction "P2.2_20") (pintype "unspecified"))
    )
    (net (code "40") (name "P23") (class "Default")
      (node (ref "H1") (pin "25") (pinfunction "25_25") (pintype "unspecified"))
      (node (ref "H1") (pin "26") (pinfunction "26_26") (pintype "unspecified"))
      (node (ref "U1") (pin "21") (pinfunction "P2.3_21") (pintype "unspecified"))
    )
    (net (code "41") (name "P24") (class "Default")
      (node (ref "H1") (pin "23") (pinfunction "23_23") (pintype "unspecified"))
      (node (ref "H1") (pin "24") (pinfunction "24_24") (pintype "unspecified"))
      (node (ref "U1") (pin "22") (pinfunction "P2.4_22") (pintype "unspecified"))
    )
    (net (code "42") (name "P25") (class "Default")
      (node (ref "H1") (pin "21") (pinfunction "21_21") (pintype "unspecified"))
      (node (ref "H1") (pin "22") (pinfunction "22_22") (pintype "unspecified"))
      (node (ref "U1") (pin "23") (pinfunction "P2.5_23") (pintype "unspecified"))
    )
    (net (code "43") (name "P26") (class "Default")
      (node (ref "H1") (pin "19") (pinfunction "19_19") (pintype "unspecified"))
      (node (ref "H1") (pin "20") (pinfunction "20_20") (pintype "unspecified"))
      (node (ref "U1") (pin "24") (pinfunction "P2.6_24") (pintype "unspecified"))
    )
    (net (code "44") (name "P27") (class "Default")
      (node (ref "H1") (pin "17") (pinfunction "17_17") (pintype "unspecified"))
      (node (ref "H1") (pin "18") (pinfunction "18_18") (pintype "unspecified"))
      (node (ref "U1") (pin "25") (pinfunction "P2.7_25") (pintype "unspecified"))
    )
    (net (code "45") (name "P30") (class "Default")
      (node (ref "H2") (pin "17") (pinfunction "17_17") (pintype "unspecified"))
      (node (ref "H2") (pin "18") (pinfunction "18_18") (pintype "unspecified"))
      (node (ref "H8") (pin "3") (pinfunction "3_3") (pintype "unspecified"))
      (node (ref "TXD") (pin "2") (pinfunction "2_2") (pintype "unspecified"))
      (node (ref "U1") (pin "5") (pinfunction "RXD/P3.0_5") (pintype "unspecified"))
    )
    (net (code "46") (name "P31") (class "Default")
      (node (ref "H2") (pin "19") (pinfunction "19_19") (pintype "unspecified"))
      (node (ref "H2") (pin "20") (pinfunction "20_20") (pintype "unspecified"))
      (node (ref "H8") (pin "4") (pinfunction "4_4") (pintype "unspecified"))
      (node (ref "RXD") (pin "2") (pinfunction "2_2") (pintype "unspecified"))
      (node (ref "U1") (pin "7") (pinfunction "TXD/P3.1_7") (pintype "unspecified"))
    )
    (net (code "47") (name "P32") (class "Default")
      (node (ref "H2") (pin "21") (pinfunction "21_21") (pintype "unspecified"))
      (node (ref "H2") (pin "22") (pinfunction "22_22") (pintype "unspecified"))
      (node (ref "U1") (pin "8") (pinfunction "INT0#/P3.2_8") (pintype "unspecified"))
    )
    (net (code "48") (name "P33") (class "Default")
      (node (ref "H2") (pin "23") (pinfunction "23_23") (pintype "unspecified"))
      (node (ref "H2") (pin "24") (pinfunction "24_24") (pintype "unspecified"))
      (node (ref "U1") (pin "9") (pinfunction "INT1#/P3.3_9") (pintype "unspecified"))
    )
    (net (code "49") (name "P34") (class "Default")
      (node (ref "H2") (pin "25") (pinfunction "25_25") (pintype "unspecified"))
      (node (ref "H2") (pin "26") (pinfunction "26_26") (pintype "unspecified"))
      (node (ref "U1") (pin "10") (pinfunction "T0/P3.4_10") (pintype "unspecified"))
    )
    (net (code "50") (name "P35") (class "Default")
      (node (ref "H2") (pin "27") (pinfunction "27_27") (pintype "unspecified"))
      (node (ref "H2") (pin "28") (pinfunction "28_28") (pintype "unspecified"))
      (node (ref "U1") (pin "11") (pinfunction "T1/P3.5_11") (pintype "unspecified"))
    )
    (net (code "51") (name "P36") (class "Default")
      (node (ref "H2") (pin "29") (pinfunction "29_29") (pintype "unspecified"))
      (node (ref "H2") (pin "30") (pinfunction "30_30") (pintype "unspecified"))
      (node (ref "U1") (pin "12") (pinfunction "P3.6/WR#_12") (pintype "unspecified"))
    )
    (net (code "52") (name "P37") (class "Default")
      (node (ref "H2") (pin "31") (pinfunction "31_31") (pintype "unspecified"))
      (node (ref "H2") (pin "32") (pinfunction "32_32") (pintype "unspecified"))
      (node (ref "U1") (pin "13") (pinfunction "P3.7/RD#_13") (pintype "unspecified"))
    )
    (net (code "53") (name "P40") (class "Default")
      (node (ref "J1") (pin "1") (pinfunction "1_1") (pintype "input"))
      (node (ref "J1") (pin "2") (pinfunction "2_2") (pintype "input"))
      (node (ref "U1") (pin "17") (pinfunction "P4.0_17") (pintype "unspecified"))
    )
    (net (code "54") (name "P41") (class "Default")
      (node (ref "J1") (pin "3") (pinfunction "3_3") (pintype "input"))
      (node (ref "J1") (pin "4") (pinfunction "4_4") (pintype "input"))
      (node (ref "U1") (pin "28") (pinfunction "P4.1_28") (pintype "unspecified"))
    )
    (net (code "55") (name "P42") (class "Default")
      (node (ref "J1") (pin "5") (pinfunction "5_5") (pintype "input"))
      (node (ref "J1") (pin "6") (pinfunction "6_6") (pintype "input"))
      (node (ref "U1") (pin "39") (pinfunction "P4.2/INT3#_39") (pintype "unspecified"))
    )
    (net (code "56") (name "P43") (class "Default")
      (node (ref "J1") (pin "7") (pinfunction "7_7") (pintype "input"))
      (node (ref "J1") (pin "8") (pinfunction "8_8") (pintype "input"))
      (node (ref "U1") (pin "6") (pinfunction "P4.3/INT2#_6") (pintype "unspecified"))
    )
    (net (code "57") (name "P44") (class "Default")
      (node (ref "J1") (pin "10") (pinfunction "10_10") (pintype "input"))
      (node (ref "J1") (pin "9") (pinfunction "9_9") (pintype "input"))
      (node (ref "U1") (pin "26") (pinfunction "PSEN#/P4.4_26") (pintype "unspecified"))
    )
    (net (code "58") (name "P45") (class "Default")
      (node (ref "J1") (pin "11") (pinfunction "11_11") (pintype "input"))
      (node (ref "J1") (pin "12") (pinfunction "12_12") (pintype "input"))
      (node (ref "U1") (pin "27") (pinfunction "ALE/P4.5_27") (pintype "unspecified"))
    )
    (net (code "59") (name "P46") (class "Default")
      (node (ref "J1") (pin "13") (pinfunction "13_13") (pintype "input"))
      (node (ref "J1") (pin "14") (pinfunction "14_14") (pintype "input"))
      (node (ref "U1") (pin "29") (pinfunction "EA#/P4.6_29") (pintype "unspecified"))
    )
    (net (code "60") (name "RST") (class "Default")
      (node (ref "C1") (pin "2") (pinfunction "2_2") (pintype "unspecified"))
      (node (ref "R1") (pin "1") (pinfunction "1_1") (pintype "unspecified"))
      (node (ref "RESET") (pin "3") (pinfunction "3_3") (pintype "unspecified"))
      (node (ref "RESET") (pin "4") (pinfunction "4_4") (pintype "unspecified"))
      (node (ref "U1") (pin "4") (pinfunction "RST_4") (pintype "unspecified"))
    )
    (net (code "61") (name "VCC") (class "Default")
      (node (ref "ON") (pin "4") (pinfunction "4_4") (pintype "unspecified"))
      (node (ref "ON") (pin "5") (pinfunction "5_5") (pintype "unspecified"))
      (node (ref "POWERIN") (pin "1") (pinfunction "1_1") (pintype "input"))
      (node (ref "USB1") (pin "A9") (pinfunction "VBUS_A9") (pintype "unspecified"))
      (node (ref "USB1") (pin "B9") (pinfunction "VBUS_B9") (pintype "unspecified"))
    )
    (net (code "62") (name "VCCX") (class "Default")
      (node (ref "F1") (pin "1") (pinfunction "1_1") (pintype "unspecified"))
      (node (ref "ON") (pin "6") (pinfunction "6_6") (pintype "unspecified"))
    )
    (net (code "63") (name "XTAL1") (class "Default")
      (node (ref "C5") (pin "1") (pinfunction "1_1") (pintype "unspecified"))
      (node (ref "U1") (pin "15") (pinfunction "XTAL1_15") (pintype "unspecified"))
      (node (ref "X1") (pin "1") (pinfunction "1_1") (pintype "unspecified"))
    )
    (net (code "64") (name "XTAL2") (class "Default")
      (node (ref "C4") (pin "2") (pinfunction "2_2") (pintype "unspecified"))
      (node (ref "U1") (pin "14") (pinfunction "XTAL2_14") (pintype "unspecified"))
      (node (ref "X1") (pin "2") (pinfunction "2_2") (pintype "unspecified"))
    )
    (net (code "65") (name "unconnected-(hole1-GND-Pad1)") (class "Default")
      (node (ref "hole1") (pin "1") (pinfunction "GND_1") (pintype "input+no_connect"))
    )
    (net (code "66") (name "unconnected-(hole2-GND-Pad1)") (class "Default")
      (node (ref "hole2") (pin "1") (pinfunction "GND_1") (pintype "input+no_connect"))
    )
    (net (code "67") (name "unconnected-(hole3-GND-Pad1)") (class "Default")
      (node (ref "hole3") (pin "1") (pinfunction "GND_1") (pintype "input+no_connect"))
    )
    (net (code "68") (name "unconnected-(hole4-GND-Pad1)") (class "Default")
      (node (ref "hole4") (pin "1") (pinfunction "GND_1") (pintype "input+no_connect"))
    )
  )
)
